# 17_-_LVDS_CSI_LCD_TSC.net
KiCad netlist of a schematic drawn in Altium Designer
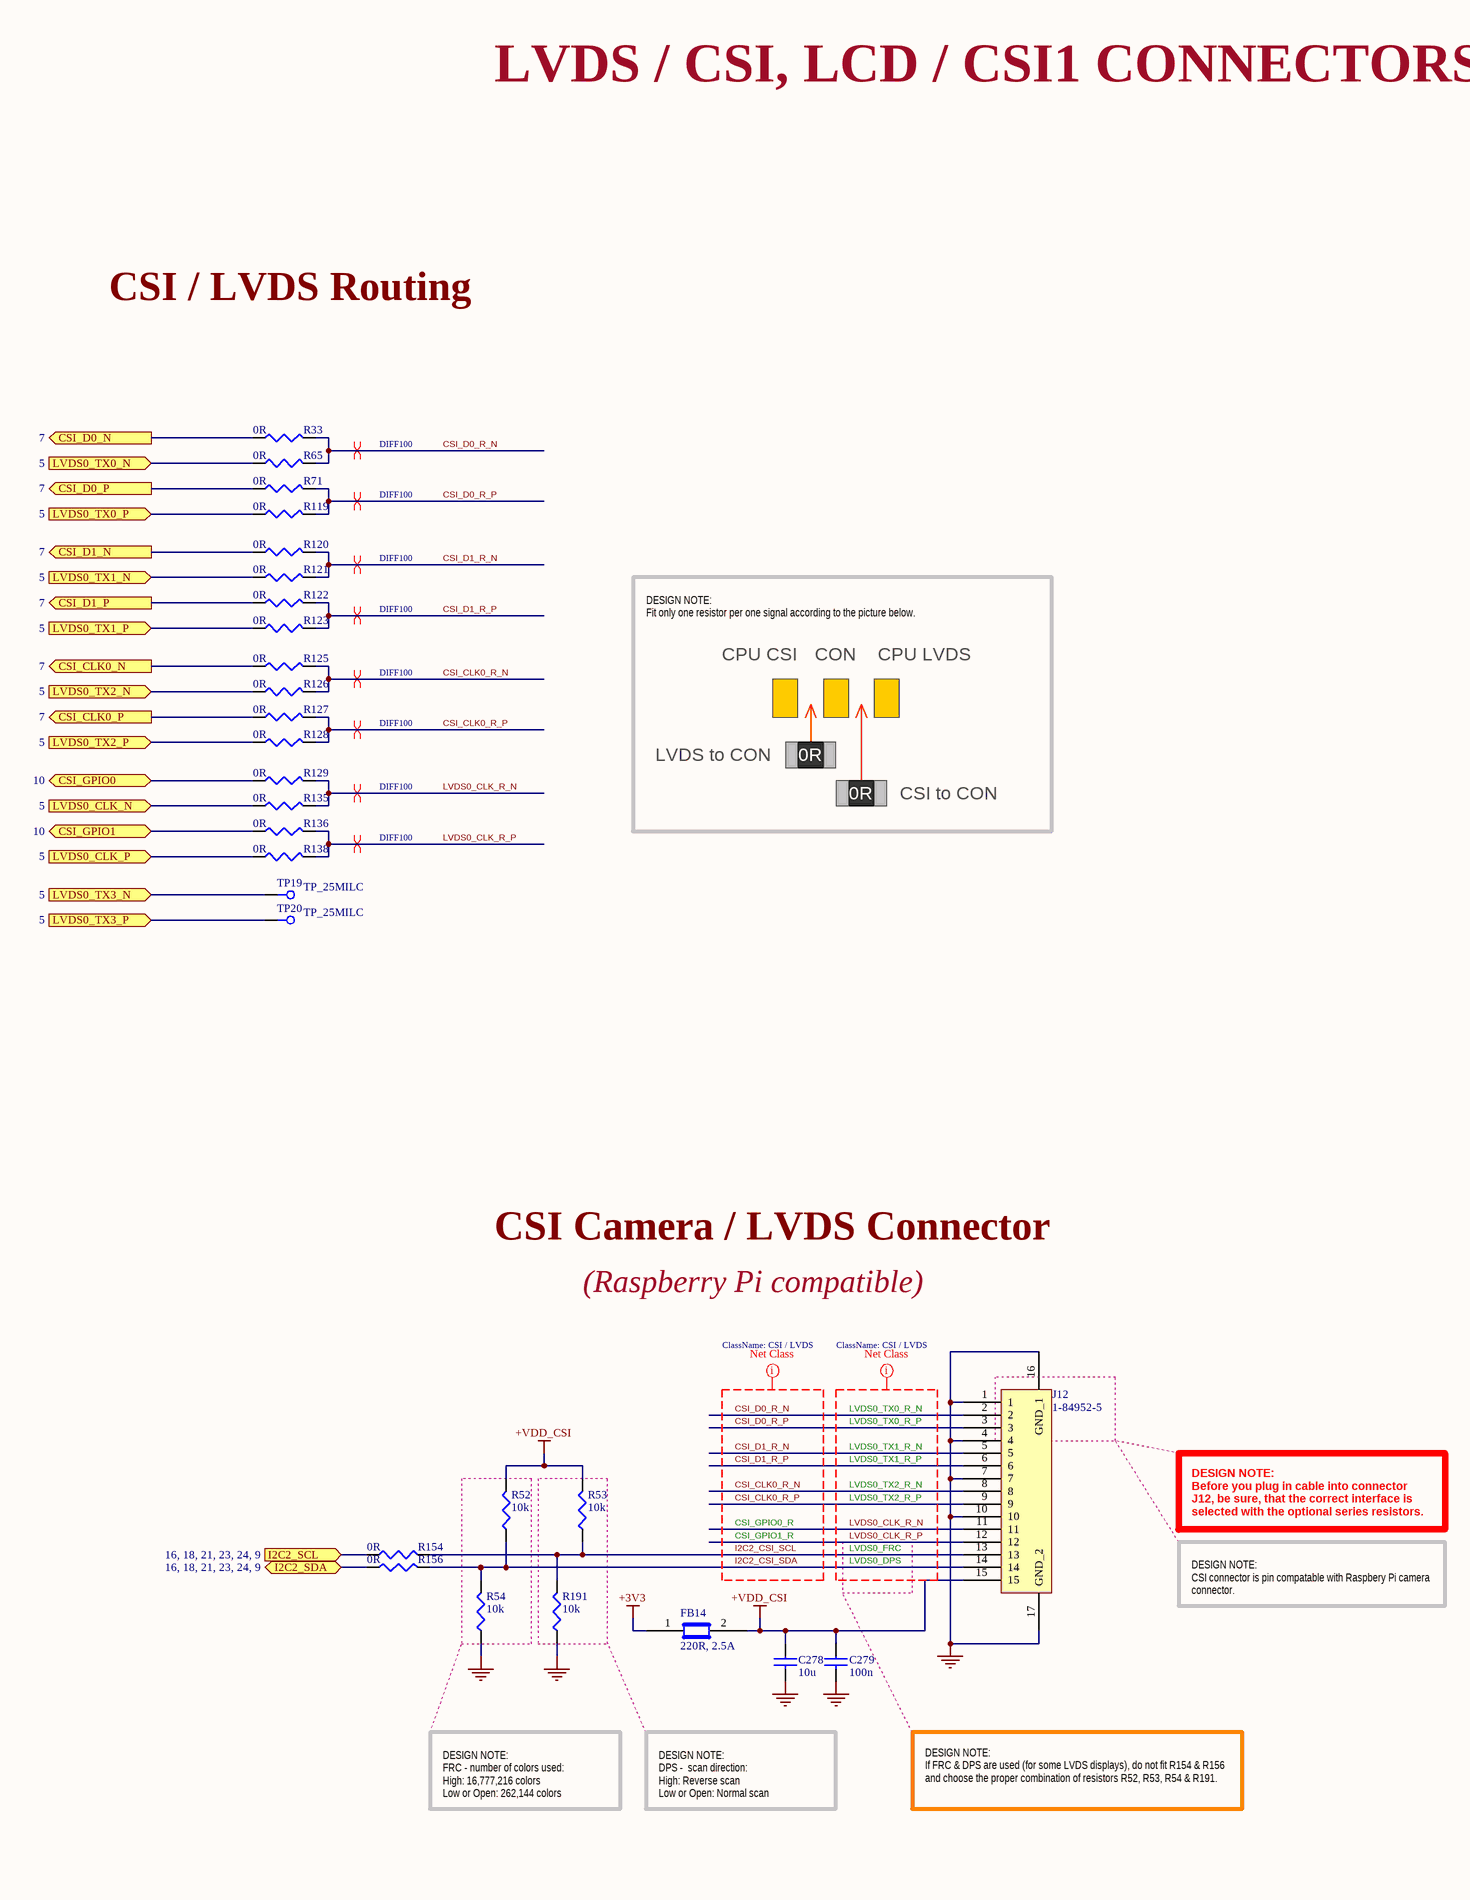
[diagram p0: [17] - LVDS, CSI, LCD, TSC.SchDoc, left]
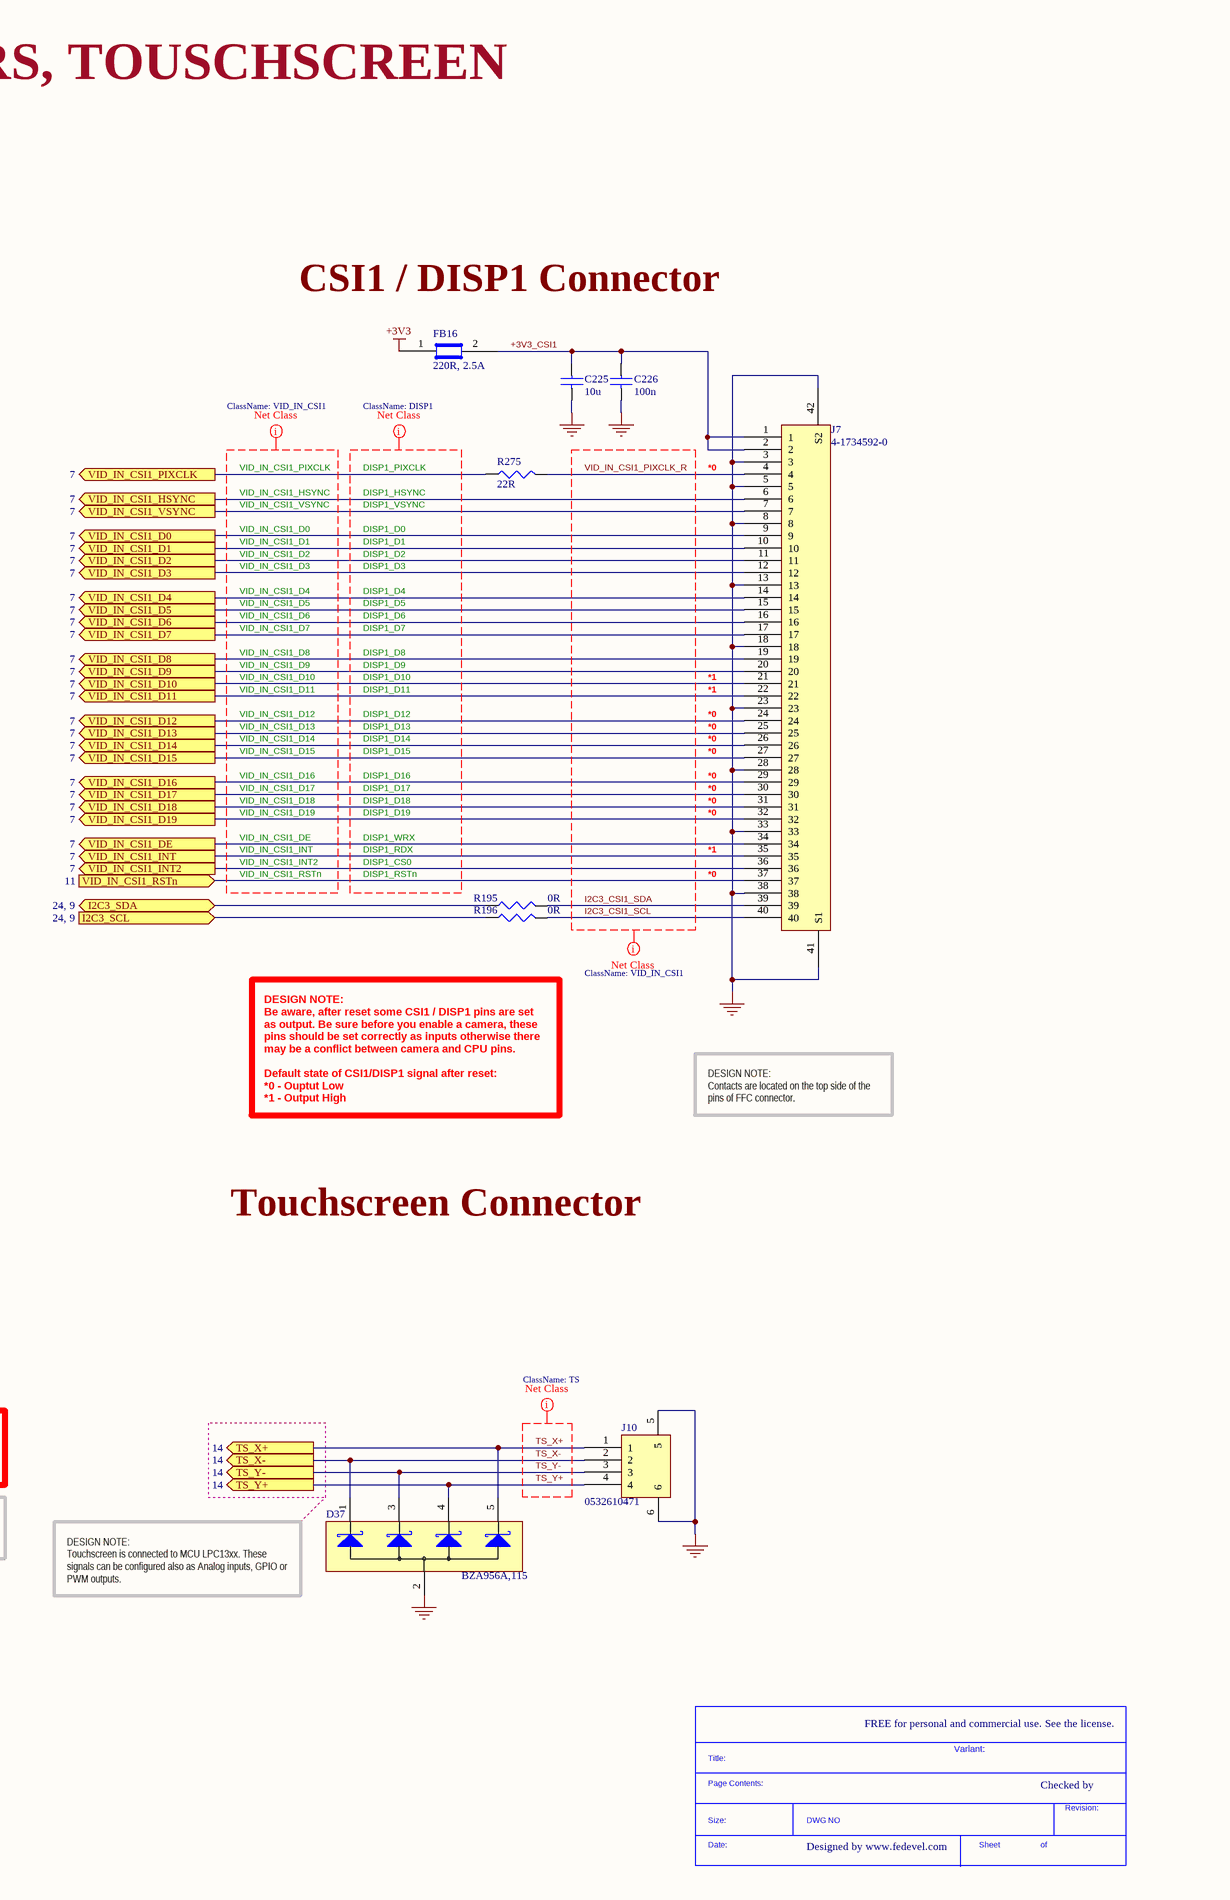
[diagram p1: [17] - LVDS, CSI, LCD, TSC.SchDoc, right]

(export (version "E")
  (design (tool "Eeschema 10.0.6"))
  (components
    (comp (ref "C225")
      (value "10u")
      (footprint "C0603")
      (description "CAP CER 10UF 6.3V X5R 20% 0603")
      (fields
        (field (name "MANUFACTURER") "TDK Corporation")
        (field (name "MANUFACTURER PART NUMBER") "C1608X5R0J106M")
      )
      (libsource (lib "Integrated_Library_FEDEVEL_APR_2015") (part "C1608X5R0J106M"))
    )
    (comp (ref "C226")
      (value "100n")
      (footprint "C0402")
      (description "CAP CER .10UF 50V X5R 10% 0402")
      (fields
        (field (name "MANUFACTURER") "TDK Corporation")
        (field (name "MANUFACTURER PART NUMBER") "C1005X5R1H104K")
      )
      (libsource (lib "Integrated_Library_FEDEVEL_APR_2015") (part "C1005X5R1H104K"))
    )
    (comp (ref "C278")
      (value "10u")
      (footprint "C0603")
      (description "CAP CER 10UF 6.3V X5R 20% 0603")
      (fields
        (field (name "MANUFACTURER") "TDK Corporation")
        (field (name "MANUFACTURER PART NUMBER") "C1608X5R0J106M")
      )
      (libsource (lib "Integrated_Library_FEDEVEL_APR_2015") (part "C1608X5R0J106M"))
    )
    (comp (ref "C279")
      (value "100n")
      (footprint "C0402")
      (description "CAP CER .10UF 50V X5R 10% 0402")
      (fields
        (field (name "MANUFACTURER") "TDK Corporation")
        (field (name "MANUFACTURER PART NUMBER") "C1005X5R1H104K")
      )
      (libsource (lib "Integrated_Library_FEDEVEL_APR_2015") (part "C1005X5R1H104K"))
    )
    (comp (ref "D37")
      (value "BZA956A,115")
      (footprint "SOT665")
      (description "TVS ZENER QUAD 5.6V SOT665")
      (fields (field (name "MANUFACTURER") "NXP Semiconductors") (field (name ".CREATOR") "MM"))
      (libsource (lib "Integrated_Library_FEDEVEL_APR_2015") (part "BZA956A,115"))
    )
    (comp (ref "FB14")
      (value "220R, 2.5A")
      (footprint "C0603")
      (description "FERRITE CHIP 220 OHM 2500MA 0603")
      (fields
        (field (name "MANUFACTURER") "Murata Electronics North America")
        (field (name "MANUFACTURER PART NUMBER") "BLM18SG221TN1D")
      )
      (libsource (lib "Integrated_Library_FEDEVEL_APR_2015") (part "BLM18SG221TN1D"))
    )
    (comp (ref "FB16")
      (value "220R, 2.5A")
      (footprint "C0603")
      (description "FERRITE CHIP 220 OHM 2500MA 0603")
      (fields
        (field (name "MANUFACTURER") "Murata Electronics North America")
        (field (name "MANUFACTURER PART NUMBER") "BLM18SG221TN1D")
      )
      (libsource (lib "Integrated_Library_FEDEVEL_APR_2015") (part "BLM18SG221TN1D"))
    )
    (comp (ref "J7")
      (value "4-1734592-0")
      (footprint "4-1734592-0")
      (description "CONN FPC BOTTOM 40POS 0.50MM R/A")
      (fields
        (field (name "MANUFACTURER") "TE Connectivity")
        (field (name ".CREATOR") "MM")
        (field (name ".CHECKED PCB") "MM")
        (field (name ".CHECKED SCH") "MM")
      )
      (libsource (lib "Integrated_Library_FEDEVEL_APR_2015") (part "4-1734592-0"))
    )
    (comp (ref "J10")
      (value "0532610471")
      (footprint "0532610471")
      (description "CONN HEADER 4POS 1.25MM R/A SMD")
      (fields (field (name "MANUFACTURER") "Molex Inc") (field (name ".CREATOR") "MM"))
      (libsource (lib "Integrated_Library_FEDEVEL_APR_2015") (part "0532610471"))
    )
    (comp (ref "J12")
      (value "1-84952-5")
      (footprint "ZIF_RA_BOTTOM_15x1mm")
      (description "CONN FPC BOTTOM 15POS 1.00MM R/A")
      (fields
        (field (name "MANUFACTURER") "TE Connectivity")
        (field (name ".CREATOR") "MM")
        (field (name ".CHECKED PCB") "MM")
        (field (name ".CHECKED SCH") "MM")
      )
      (libsource (lib "Integrated_Library_FEDEVEL_APR_2015") (part "1-84952-5"))
    )
    (comp (ref "R33")
      (value "0R")
      (footprint "R0402")
      (description "RES 0.0 OHM 1/16W 0402 SMD")
      (fields
        (field (name "MANUFACTURER") "Yageo")
        (field (name "MANUFACTURER PART NUMBER") "RC0402JR-070RL")
      )
      (libsource (lib "Integrated_Library_FEDEVEL_APR_2015") (part "RC0402JR-070RL"))
    )
    (comp (ref "R52")
      (value "10k")
      (footprint "R0402")
      (description "RES 10.0K OHM 1/16W 1% 0402 SMD")
      (fields
        (field (name "MANUFACTURER") "Yageo")
        (field (name "MANUFACTURER PART NUMBER") "RC0402FR-0710KL")
      )
      (libsource (lib "Integrated_Library_FEDEVEL_APR_2015") (part "RC0402FR-0710KL"))
    )
    (comp (ref "R53")
      (value "10k")
      (footprint "R0402")
      (description "RES 10.0K OHM 1/16W 1% 0402 SMD")
      (fields
        (field (name "MANUFACTURER") "Yageo")
        (field (name "MANUFACTURER PART NUMBER") "RC0402FR-0710KL")
      )
      (libsource (lib "Integrated_Library_FEDEVEL_APR_2015") (part "RC0402FR-0710KL"))
    )
    (comp (ref "R54")
      (value "10k")
      (footprint "R0402")
      (description "RES 10.0K OHM 1/16W 1% 0402 SMD")
      (fields
        (field (name "MANUFACTURER") "Yageo")
        (field (name "MANUFACTURER PART NUMBER") "RC0402FR-0710KL")
      )
      (libsource (lib "Integrated_Library_FEDEVEL_APR_2015") (part "RC0402FR-0710KL"))
    )
    (comp (ref "R65")
      (value "0R")
      (footprint "R0402")
      (description "RES 0.0 OHM 1/16W 0402 SMD")
      (fields
        (field (name "MANUFACTURER") "Yageo")
        (field (name "MANUFACTURER PART NUMBER") "RC0402JR-070RL")
      )
      (libsource (lib "Integrated_Library_FEDEVEL_APR_2015") (part "RC0402JR-070RL"))
    )
    (comp (ref "R71")
      (value "0R")
      (footprint "R0402")
      (description "RES 0.0 OHM 1/16W 0402 SMD")
      (fields
        (field (name "MANUFACTURER") "Yageo")
        (field (name "MANUFACTURER PART NUMBER") "RC0402JR-070RL")
      )
      (libsource (lib "Integrated_Library_FEDEVEL_APR_2015") (part "RC0402JR-070RL"))
    )
    (comp (ref "R119")
      (value "0R")
      (footprint "R0402")
      (description "RES 0.0 OHM 1/16W 0402 SMD")
      (fields
        (field (name "MANUFACTURER") "Yageo")
        (field (name "MANUFACTURER PART NUMBER") "RC0402JR-070RL")
      )
      (libsource (lib "Integrated_Library_FEDEVEL_APR_2015") (part "RC0402JR-070RL"))
    )
    (comp (ref "R120")
      (value "0R")
      (footprint "R0402")
      (description "RES 0.0 OHM 1/16W 0402 SMD")
      (fields
        (field (name "MANUFACTURER") "Yageo")
        (field (name "MANUFACTURER PART NUMBER") "RC0402JR-070RL")
      )
      (libsource (lib "Integrated_Library_FEDEVEL_APR_2015") (part "RC0402JR-070RL"))
    )
    (comp (ref "R121")
      (value "0R")
      (footprint "R0402")
      (description "RES 0.0 OHM 1/16W 0402 SMD")
      (fields
        (field (name "MANUFACTURER") "Yageo")
        (field (name "MANUFACTURER PART NUMBER") "RC0402JR-070RL")
      )
      (libsource (lib "Integrated_Library_FEDEVEL_APR_2015") (part "RC0402JR-070RL"))
    )
    (comp (ref "R122")
      (value "0R")
      (footprint "R0402")
      (description "RES 0.0 OHM 1/16W 0402 SMD")
      (fields
        (field (name "MANUFACTURER") "Yageo")
        (field (name "MANUFACTURER PART NUMBER") "RC0402JR-070RL")
      )
      (libsource (lib "Integrated_Library_FEDEVEL_APR_2015") (part "RC0402JR-070RL"))
    )
    (comp (ref "R123")
      (value "0R")
      (footprint "R0402")
      (description "RES 0.0 OHM 1/16W 0402 SMD")
      (fields
        (field (name "MANUFACTURER") "Yageo")
        (field (name "MANUFACTURER PART NUMBER") "RC0402JR-070RL")
      )
      (libsource (lib "Integrated_Library_FEDEVEL_APR_2015") (part "RC0402JR-070RL"))
    )
    (comp (ref "R125")
      (value "0R")
      (footprint "R0402")
      (description "RES 0.0 OHM 1/16W 0402 SMD")
      (fields
        (field (name "MANUFACTURER") "Yageo")
        (field (name "MANUFACTURER PART NUMBER") "RC0402JR-070RL")
      )
      (libsource (lib "Integrated_Library_FEDEVEL_APR_2015") (part "RC0402JR-070RL"))
    )
    (comp (ref "R126")
      (value "0R")
      (footprint "R0402")
      (description "RES 0.0 OHM 1/16W 0402 SMD")
      (fields
        (field (name "MANUFACTURER") "Yageo")
        (field (name "MANUFACTURER PART NUMBER") "RC0402JR-070RL")
      )
      (libsource (lib "Integrated_Library_FEDEVEL_APR_2015") (part "RC0402JR-070RL"))
    )
    (comp (ref "R127")
      (value "0R")
      (footprint "R0402")
      (description "RES 0.0 OHM 1/16W 0402 SMD")
      (fields
        (field (name "MANUFACTURER") "Yageo")
        (field (name "MANUFACTURER PART NUMBER") "RC0402JR-070RL")
      )
      (libsource (lib "Integrated_Library_FEDEVEL_APR_2015") (part "RC0402JR-070RL"))
    )
    (comp (ref "R128")
      (value "0R")
      (footprint "R0402")
      (description "RES 0.0 OHM 1/16W 0402 SMD")
      (fields
        (field (name "MANUFACTURER") "Yageo")
        (field (name "MANUFACTURER PART NUMBER") "RC0402JR-070RL")
      )
      (libsource (lib "Integrated_Library_FEDEVEL_APR_2015") (part "RC0402JR-070RL"))
    )
    (comp (ref "R129")
      (value "0R")
      (footprint "R0402")
      (description "RES 0.0 OHM 1/16W 0402 SMD")
      (fields
        (field (name "MANUFACTURER") "Yageo")
        (field (name "MANUFACTURER PART NUMBER") "RC0402JR-070RL")
      )
      (libsource (lib "Integrated_Library_FEDEVEL_APR_2015") (part "RC0402JR-070RL"))
    )
    (comp (ref "R135")
      (value "0R")
      (footprint "R0402")
      (description "RES 0.0 OHM 1/16W 0402 SMD")
      (fields
        (field (name "MANUFACTURER") "Yageo")
        (field (name "MANUFACTURER PART NUMBER") "RC0402JR-070RL")
      )
      (libsource (lib "Integrated_Library_FEDEVEL_APR_2015") (part "RC0402JR-070RL"))
    )
    (comp (ref "R136")
      (value "0R")
      (footprint "R0402")
      (description "RES 0.0 OHM 1/16W 0402 SMD")
      (fields
        (field (name "MANUFACTURER") "Yageo")
        (field (name "MANUFACTURER PART NUMBER") "RC0402JR-070RL")
      )
      (libsource (lib "Integrated_Library_FEDEVEL_APR_2015") (part "RC0402JR-070RL"))
    )
    (comp (ref "R138")
      (value "0R")
      (footprint "R0402")
      (description "RES 0.0 OHM 1/16W 0402 SMD")
      (fields
        (field (name "MANUFACTURER") "Yageo")
        (field (name "MANUFACTURER PART NUMBER") "RC0402JR-070RL")
      )
      (libsource (lib "Integrated_Library_FEDEVEL_APR_2015") (part "RC0402JR-070RL"))
    )
    (comp (ref "R154")
      (value "0R")
      (footprint "R0402")
      (description "RES 0.0 OHM 1/16W 0402 SMD")
      (fields
        (field (name "MANUFACTURER") "Yageo")
        (field (name "MANUFACTURER PART NUMBER") "RC0402JR-070RL")
      )
      (libsource (lib "Integrated_Library_FEDEVEL_APR_2015") (part "RC0402JR-070RL"))
    )
    (comp (ref "R156")
      (value "0R")
      (footprint "R0402")
      (description "RES 0.0 OHM 1/16W 0402 SMD")
      (fields
        (field (name "MANUFACTURER") "Yageo")
        (field (name "MANUFACTURER PART NUMBER") "RC0402JR-070RL")
      )
      (libsource (lib "Integrated_Library_FEDEVEL_APR_2015") (part "RC0402JR-070RL"))
    )
    (comp (ref "R191")
      (value "10k")
      (footprint "R0402")
      (description "RES 10.0K OHM 1/16W 1% 0402 SMD")
      (fields
        (field (name "MANUFACTURER") "Yageo")
        (field (name "MANUFACTURER PART NUMBER") "RC0402FR-0710KL")
      )
      (libsource (lib "Integrated_Library_FEDEVEL_APR_2015") (part "RC0402FR-0710KL"))
    )
    (comp (ref "R195")
      (value "0R")
      (footprint "R0402")
      (description "RES 0.0 OHM 1/16W 0402 SMD")
      (fields
        (field (name "MANUFACTURER") "Yageo")
        (field (name "MANUFACTURER PART NUMBER") "RC0402JR-070RL")
      )
      (libsource (lib "Integrated_Library_FEDEVEL_APR_2015") (part "RC0402JR-070RL"))
    )
    (comp (ref "R196")
      (value "0R")
      (footprint "R0402")
      (description "RES 0.0 OHM 1/16W 0402 SMD")
      (fields
        (field (name "MANUFACTURER") "Yageo")
        (field (name "MANUFACTURER PART NUMBER") "RC0402JR-070RL")
      )
      (libsource (lib "Integrated_Library_FEDEVEL_APR_2015") (part "RC0402JR-070RL"))
    )
    (comp (ref "R275")
      (value "22R")
      (footprint "R0402")
      (description "RES 22.0 OHM 1/16W 1% 0402 SMD")
      (fields
        (field (name "MANUFACTURER") "Yageo")
        (field (name "MANUFACTURER PART NUMBER") "RC0402FR-0722RL")
      )
      (libsource (lib "Integrated_Library_FEDEVEL_APR_2015") (part "RC0402FR-0722RL"))
    )
    (comp (ref "TP19")
      (value "TP_25MILC")
      (footprint "TP_25C")
      (description "Test Point 25mil")
      (libsource (lib "Integrated_Library_FEDEVEL_APR_2015") (part "TP_25MILC"))
    )
    (comp (ref "TP20")
      (value "TP_25MILC")
      (footprint "TP_25C")
      (description "Test Point 25mil")
      (libsource (lib "Integrated_Library_FEDEVEL_APR_2015") (part "TP_25MILC"))
    )
  )
  (nets
    (net (code "1") (name "+3V3") (class "Default")
      (node (ref "FB14") (pin "1") (pinfunction "1_1") (pintype "passive"))
      (node (ref "FB16") (pin "1") (pinfunction "1_1") (pintype "passive"))
    )
    (net (code "2") (name "+VDD_CSI") (class "Default")
      (node (ref "C278") (pin "1") (pinfunction "1_1") (pintype "passive"))
      (node (ref "C279") (pin "1") (pinfunction "1_1") (pintype "passive"))
      (node (ref "FB14") (pin "2") (pinfunction "2_2") (pintype "passive"))
      (node (ref "J12") (pin "15") (pinfunction "15_15") (pintype "passive"))
      (node (ref "R52") (pin "2") (pinfunction "2_2") (pintype "passive"))
      (node (ref "R53") (pin "2") (pinfunction "2_2") (pintype "passive"))
    )
    (net (code "3") (name "/+3V3_CSI1") (class "Default")
      (node (ref "C225") (pin "1") (pinfunction "1_1") (pintype "passive"))
      (node (ref "C226") (pin "1") (pinfunction "1_1") (pintype "passive"))
      (node (ref "FB16") (pin "2") (pinfunction "2_2") (pintype "passive"))
      (node (ref "J7") (pin "1") (pinfunction "1_1") (pintype "passive"))
      (node (ref "J7") (pin "2") (pinfunction "2_2") (pintype "passive"))
    )
    (net (code "4") (name "/CSI_CLK0_N") (class "Default")
      (node (ref "R125") (pin "1") (pinfunction "1_1") (pintype "passive"))
    )
    (net (code "5") (name "/CSI_CLK0_P") (class "Default")
      (node (ref "R127") (pin "1") (pinfunction "1_1") (pintype "passive"))
    )
    (net (code "6") (name "/CSI_CLK0_R_N") (class "Default")
      (node (ref "J12") (pin "8") (pinfunction "8_8") (pintype "passive"))
      (node (ref "R125") (pin "2") (pinfunction "2_2") (pintype "passive"))
      (node (ref "R126") (pin "2") (pinfunction "2_2") (pintype "passive"))
    )
    (net (code "7") (name "/CSI_CLK0_R_P") (class "Default")
      (node (ref "J12") (pin "9") (pinfunction "9_9") (pintype "passive"))
      (node (ref "R127") (pin "2") (pinfunction "2_2") (pintype "passive"))
      (node (ref "R128") (pin "2") (pinfunction "2_2") (pintype "passive"))
    )
    (net (code "8") (name "/CSI_D0_N") (class "Default")
      (node (ref "R33") (pin "1") (pinfunction "1_1") (pintype "passive"))
    )
    (net (code "9") (name "/CSI_D0_P") (class "Default")
      (node (ref "R71") (pin "1") (pinfunction "1_1") (pintype "passive"))
    )
    (net (code "10") (name "/CSI_D0_R_N") (class "Default")
      (node (ref "J12") (pin "2") (pinfunction "2_2") (pintype "passive"))
      (node (ref "R33") (pin "2") (pinfunction "2_2") (pintype "passive"))
      (node (ref "R65") (pin "2") (pinfunction "2_2") (pintype "passive"))
    )
    (net (code "11") (name "/CSI_D0_R_P") (class "Default")
      (node (ref "J12") (pin "3") (pinfunction "3_3") (pintype "passive"))
      (node (ref "R119") (pin "2") (pinfunction "2_2") (pintype "passive"))
      (node (ref "R71") (pin "2") (pinfunction "2_2") (pintype "passive"))
    )
    (net (code "12") (name "/CSI_D1_N") (class "Default")
      (node (ref "R120") (pin "1") (pinfunction "1_1") (pintype "passive"))
    )
    (net (code "13") (name "/CSI_D1_P") (class "Default")
      (node (ref "R122") (pin "1") (pinfunction "1_1") (pintype "passive"))
    )
    (net (code "14") (name "/CSI_D1_R_N") (class "Default")
      (node (ref "J12") (pin "5") (pinfunction "5_5") (pintype "passive"))
      (node (ref "R120") (pin "2") (pinfunction "2_2") (pintype "passive"))
      (node (ref "R121") (pin "2") (pinfunction "2_2") (pintype "passive"))
    )
    (net (code "15") (name "/CSI_D1_R_P") (class "Default")
      (node (ref "J12") (pin "6") (pinfunction "6_6") (pintype "passive"))
      (node (ref "R122") (pin "2") (pinfunction "2_2") (pintype "passive"))
      (node (ref "R123") (pin "2") (pinfunction "2_2") (pintype "passive"))
    )
    (net (code "16") (name "/CSI_GPIO0") (class "Default")
      (node (ref "R129") (pin "1") (pinfunction "1_1") (pintype "passive"))
    )
    (net (code "17") (name "/CSI_GPIO1") (class "Default")
      (node (ref "R136") (pin "1") (pinfunction "1_1") (pintype "passive"))
    )
    (net (code "18") (name "/I2C2_CSI_SCL") (class "Default")
      (node (ref "J12") (pin "13") (pinfunction "13_13") (pintype "passive"))
      (node (ref "R154") (pin "2") (pinfunction "2_2") (pintype "passive"))
      (node (ref "R191") (pin "2") (pinfunction "2_2") (pintype "passive"))
      (node (ref "R53") (pin "1") (pinfunction "1_1") (pintype "passive"))
    )
    (net (code "19") (name "/I2C2_CSI_SDA") (class "Default")
      (node (ref "J12") (pin "14") (pinfunction "14_14") (pintype "passive"))
      (node (ref "R156") (pin "2") (pinfunction "2_2") (pintype "passive"))
      (node (ref "R52") (pin "1") (pinfunction "1_1") (pintype "passive"))
      (node (ref "R54") (pin "2") (pinfunction "2_2") (pintype "passive"))
    )
    (net (code "20") (name "/I2C2_SCL") (class "Default")
      (node (ref "R154") (pin "1") (pinfunction "1_1") (pintype "passive"))
    )
    (net (code "21") (name "/I2C2_SDA") (class "Default")
      (node (ref "R156") (pin "1") (pinfunction "1_1") (pintype "passive"))
    )
    (net (code "22") (name "/I2C3_CSI1_SCL") (class "Default")
      (node (ref "J7") (pin "40") (pinfunction "40_40") (pintype "passive"))
      (node (ref "R196") (pin "1") (pinfunction "1_1") (pintype "passive"))
    )
    (net (code "23") (name "/I2C3_CSI1_SDA") (class "Default")
      (node (ref "J7") (pin "39") (pinfunction "39_39") (pintype "passive"))
      (node (ref "R195") (pin "1") (pinfunction "1_1") (pintype "passive"))
    )
    (net (code "24") (name "/I2C3_SCL") (class "Default")
      (node (ref "R196") (pin "2") (pinfunction "2_2") (pintype "passive"))
    )
    (net (code "25") (name "/I2C3_SDA") (class "Default")
      (node (ref "R195") (pin "2") (pinfunction "2_2") (pintype "passive"))
    )
    (net (code "26") (name "/LVDS0_CLK_N") (class "Default")
      (node (ref "R135") (pin "1") (pinfunction "1_1") (pintype "passive"))
    )
    (net (code "27") (name "/LVDS0_CLK_P") (class "Default")
      (node (ref "R138") (pin "1") (pinfunction "1_1") (pintype "passive"))
    )
    (net (code "28") (name "/LVDS0_CLK_R_N") (class "Default")
      (node (ref "J12") (pin "11") (pinfunction "11_11") (pintype "passive"))
      (node (ref "R129") (pin "2") (pinfunction "2_2") (pintype "passive"))
      (node (ref "R135") (pin "2") (pinfunction "2_2") (pintype "passive"))
    )
    (net (code "29") (name "/LVDS0_CLK_R_P") (class "Default")
      (node (ref "J12") (pin "12") (pinfunction "12_12") (pintype "passive"))
      (node (ref "R136") (pin "2") (pinfunction "2_2") (pintype "passive"))
      (node (ref "R138") (pin "2") (pinfunction "2_2") (pintype "passive"))
    )
    (net (code "30") (name "/LVDS0_TX0_N") (class "Default")
      (node (ref "R65") (pin "1") (pinfunction "1_1") (pintype "passive"))
    )
    (net (code "31") (name "/LVDS0_TX0_P") (class "Default")
      (node (ref "R119") (pin "1") (pinfunction "1_1") (pintype "passive"))
    )
    (net (code "32") (name "/LVDS0_TX1_N") (class "Default")
      (node (ref "R121") (pin "1") (pinfunction "1_1") (pintype "passive"))
    )
    (net (code "33") (name "/LVDS0_TX1_P") (class "Default")
      (node (ref "R123") (pin "1") (pinfunction "1_1") (pintype "passive"))
    )
    (net (code "34") (name "/LVDS0_TX2_N") (class "Default")
      (node (ref "R126") (pin "1") (pinfunction "1_1") (pintype "passive"))
    )
    (net (code "35") (name "/LVDS0_TX2_P") (class "Default")
      (node (ref "R128") (pin "1") (pinfunction "1_1") (pintype "passive"))
    )
    (net (code "36") (name "/LVDS0_TX3_N") (class "Default")
      (node (ref "TP19") (pin "1") (pinfunction "1_1") (pintype "passive"))
    )
    (net (code "37") (name "/LVDS0_TX3_P") (class "Default")
      (node (ref "TP20") (pin "1") (pinfunction "1_1") (pintype "passive"))
    )
    (net (code "38") (name "/TS_X+") (class "Default")
      (node (ref "D37") (pin "5") (pinfunction "5_5") (pintype "passive"))
      (node (ref "J10") (pin "1") (pinfunction "1_1") (pintype "passive"))
    )
    (net (code "39") (name "/TS_X-") (class "Default")
      (node (ref "D37") (pin "1") (pinfunction "1_1") (pintype "passive"))
      (node (ref "J10") (pin "2") (pinfunction "2_2") (pintype "passive"))
    )
    (net (code "40") (name "/TS_Y+") (class "Default")
      (node (ref "D37") (pin "4") (pinfunction "4_4") (pintype "passive"))
      (node (ref "J10") (pin "4") (pinfunction "4_4") (pintype "passive"))
    )
    (net (code "41") (name "/TS_Y-") (class "Default")
      (node (ref "D37") (pin "3") (pinfunction "3_3") (pintype "passive"))
      (node (ref "J10") (pin "3") (pinfunction "3_3") (pintype "passive"))
    )
    (net (code "42") (name "/VID_IN_CSI1_D0") (class "Default")
      (node (ref "J7") (pin "9") (pinfunction "9_9") (pintype "passive"))
    )
    (net (code "43") (name "/VID_IN_CSI1_D1") (class "Default")
      (node (ref "J7") (pin "10") (pinfunction "10_10") (pintype "passive"))
    )
    (net (code "44") (name "/VID_IN_CSI1_D2") (class "Default")
      (node (ref "J7") (pin "11") (pinfunction "11_11") (pintype "passive"))
    )
    (net (code "45") (name "/VID_IN_CSI1_D3") (class "Default")
      (node (ref "J7") (pin "12") (pinfunction "12_12") (pintype "passive"))
    )
    (net (code "46") (name "/VID_IN_CSI1_D4") (class "Default")
      (node (ref "J7") (pin "14") (pinfunction "14_14") (pintype "passive"))
    )
    (net (code "47") (name "/VID_IN_CSI1_D5") (class "Default")
      (node (ref "J7") (pin "15") (pinfunction "15_15") (pintype "passive"))
    )
    (net (code "48") (name "/VID_IN_CSI1_D6") (class "Default")
      (node (ref "J7") (pin "16") (pinfunction "16_16") (pintype "passive"))
    )
    (net (code "49") (name "/VID_IN_CSI1_D7") (class "Default")
      (node (ref "J7") (pin "17") (pinfunction "17_17") (pintype "passive"))
    )
    (net (code "50") (name "/VID_IN_CSI1_D8") (class "Default")
      (node (ref "J7") (pin "19") (pinfunction "19_19") (pintype "passive"))
    )
    (net (code "51") (name "/VID_IN_CSI1_D9") (class "Default")
      (node (ref "J7") (pin "20") (pinfunction "20_20") (pintype "passive"))
    )
    (net (code "52") (name "/VID_IN_CSI1_D10") (class "Default")
      (node (ref "J7") (pin "21") (pinfunction "21_21") (pintype "passive"))
    )
    (net (code "53") (name "/VID_IN_CSI1_D11") (class "Default")
      (node (ref "J7") (pin "22") (pinfunction "22_22") (pintype "passive"))
    )
    (net (code "54") (name "/VID_IN_CSI1_D12") (class "Default")
      (node (ref "J7") (pin "24") (pinfunction "24_24") (pintype "passive"))
    )
    (net (code "55") (name "/VID_IN_CSI1_D13") (class "Default")
      (node (ref "J7") (pin "25") (pinfunction "25_25") (pintype "passive"))
    )
    (net (code "56") (name "/VID_IN_CSI1_D14") (class "Default")
      (node (ref "J7") (pin "26") (pinfunction "26_26") (pintype "passive"))
    )
    (net (code "57") (name "/VID_IN_CSI1_D15") (class "Default")
      (node (ref "J7") (pin "27") (pinfunction "27_27") (pintype "passive"))
    )
    (net (code "58") (name "/VID_IN_CSI1_D16") (class "Default")
      (node (ref "J7") (pin "29") (pinfunction "29_29") (pintype "passive"))
    )
    (net (code "59") (name "/VID_IN_CSI1_D17") (class "Default")
      (node (ref "J7") (pin "30") (pinfunction "30_30") (pintype "passive"))
    )
    (net (code "60") (name "/VID_IN_CSI1_D18") (class "Default")
      (node (ref "J7") (pin "31") (pinfunction "31_31") (pintype "passive"))
    )
    (net (code "61") (name "/VID_IN_CSI1_D19") (class "Default")
      (node (ref "J7") (pin "32") (pinfunction "32_32") (pintype "passive"))
    )
    (net (code "62") (name "/VID_IN_CSI1_DE") (class "Default")
      (node (ref "J7") (pin "34") (pinfunction "34_34") (pintype "passive"))
    )
    (net (code "63") (name "/VID_IN_CSI1_HSYNC") (class "Default")
      (node (ref "J7") (pin "6") (pinfunction "6_6") (pintype "passive"))
    )
    (net (code "64") (name "/VID_IN_CSI1_INT") (class "Default")
      (node (ref "J7") (pin "35") (pinfunction "35_35") (pintype "passive"))
    )
    (net (code "65") (name "/VID_IN_CSI1_INT2") (class "Default")
      (node (ref "J7") (pin "36") (pinfunction "36_36") (pintype "passive"))
    )
    (net (code "66") (name "/VID_IN_CSI1_PIXCLK") (class "Default")
      (node (ref "R275") (pin "1") (pinfunction "1_1") (pintype "passive"))
    )
    (net (code "67") (name "/VID_IN_CSI1_PIXCLK_R") (class "Default")
      (node (ref "J7") (pin "4") (pinfunction "4_4") (pintype "passive"))
      (node (ref "R275") (pin "2") (pinfunction "2_2") (pintype "passive"))
    )
    (net (code "68") (name "/VID_IN_CSI1_RSTn") (class "Default")
      (node (ref "J7") (pin "37") (pinfunction "37_37") (pintype "passive"))
    )
    (net (code "69") (name "/VID_IN_CSI1_VSYNC") (class "Default")
      (node (ref "J7") (pin "7") (pinfunction "7_7") (pintype "passive"))
    )
    (net (code "70") (name "GND") (class "Default")
      (node (ref "C225") (pin "2") (pinfunction "2_2") (pintype "passive"))
      (node (ref "C226") (pin "2") (pinfunction "2_2") (pintype "passive"))
      (node (ref "C278") (pin "2") (pinfunction "2_2") (pintype "passive"))
      (node (ref "C279") (pin "2") (pinfunction "2_2") (pintype "passive"))
      (node (ref "D37") (pin "2") (pinfunction "2_2") (pintype "passive"))
      (node (ref "J10") (pin "5") (pinfunction "5_5") (pintype "passive"))
      (node (ref "J10") (pin "6") (pinfunction "6_6") (pintype "passive"))
      (node (ref "J12") (pin "1") (pinfunction "1_1") (pintype "passive"))
      (node (ref "J12") (pin "10") (pinfunction "10_10") (pintype "passive"))
      (node (ref "J12") (pin "16") (pinfunction "GND_1_16") (pintype "passive"))
      (node (ref "J12") (pin "17") (pinfunction "GND_2_17") (pintype "passive"))
      (node (ref "J12") (pin "4") (pinfunction "4_4") (pintype "passive"))
      (node (ref "J12") (pin "7") (pinfunction "7_7") (pintype "passive"))
      (node (ref "J7") (pin "13") (pinfunction "13_13") (pintype "passive"))
      (node (ref "J7") (pin "18") (pinfunction "18_18") (pintype "passive"))
      (node (ref "J7") (pin "23") (pinfunction "23_23") (pintype "passive"))
      (node (ref "J7") (pin "28") (pinfunction "28_28") (pintype "passive"))
      (node (ref "J7") (pin "3") (pinfunction "3_3") (pintype "passive"))
      (node (ref "J7") (pin "33") (pinfunction "33_33") (pintype "passive"))
      (node (ref "J7") (pin "38") (pinfunction "38_38") (pintype "passive"))
      (node (ref "J7") (pin "41") (pinfunction "S1_41") (pintype "passive"))
      (node (ref "J7") (pin "42") (pinfunction "S2_42") (pintype "passive"))
      (node (ref "J7") (pin "5") (pinfunction "5_5") (pintype "passive"))
      (node (ref "J7") (pin "8") (pinfunction "8_8") (pintype "passive"))
      (node (ref "R191") (pin "1") (pinfunction "1_1") (pintype "passive"))
      (node (ref "R54") (pin "1") (pinfunction "1_1") (pintype "passive"))
    )
  )
)
